# pcb_throughhole.net
KiCad netlist of a schematic drawn in EAGLE
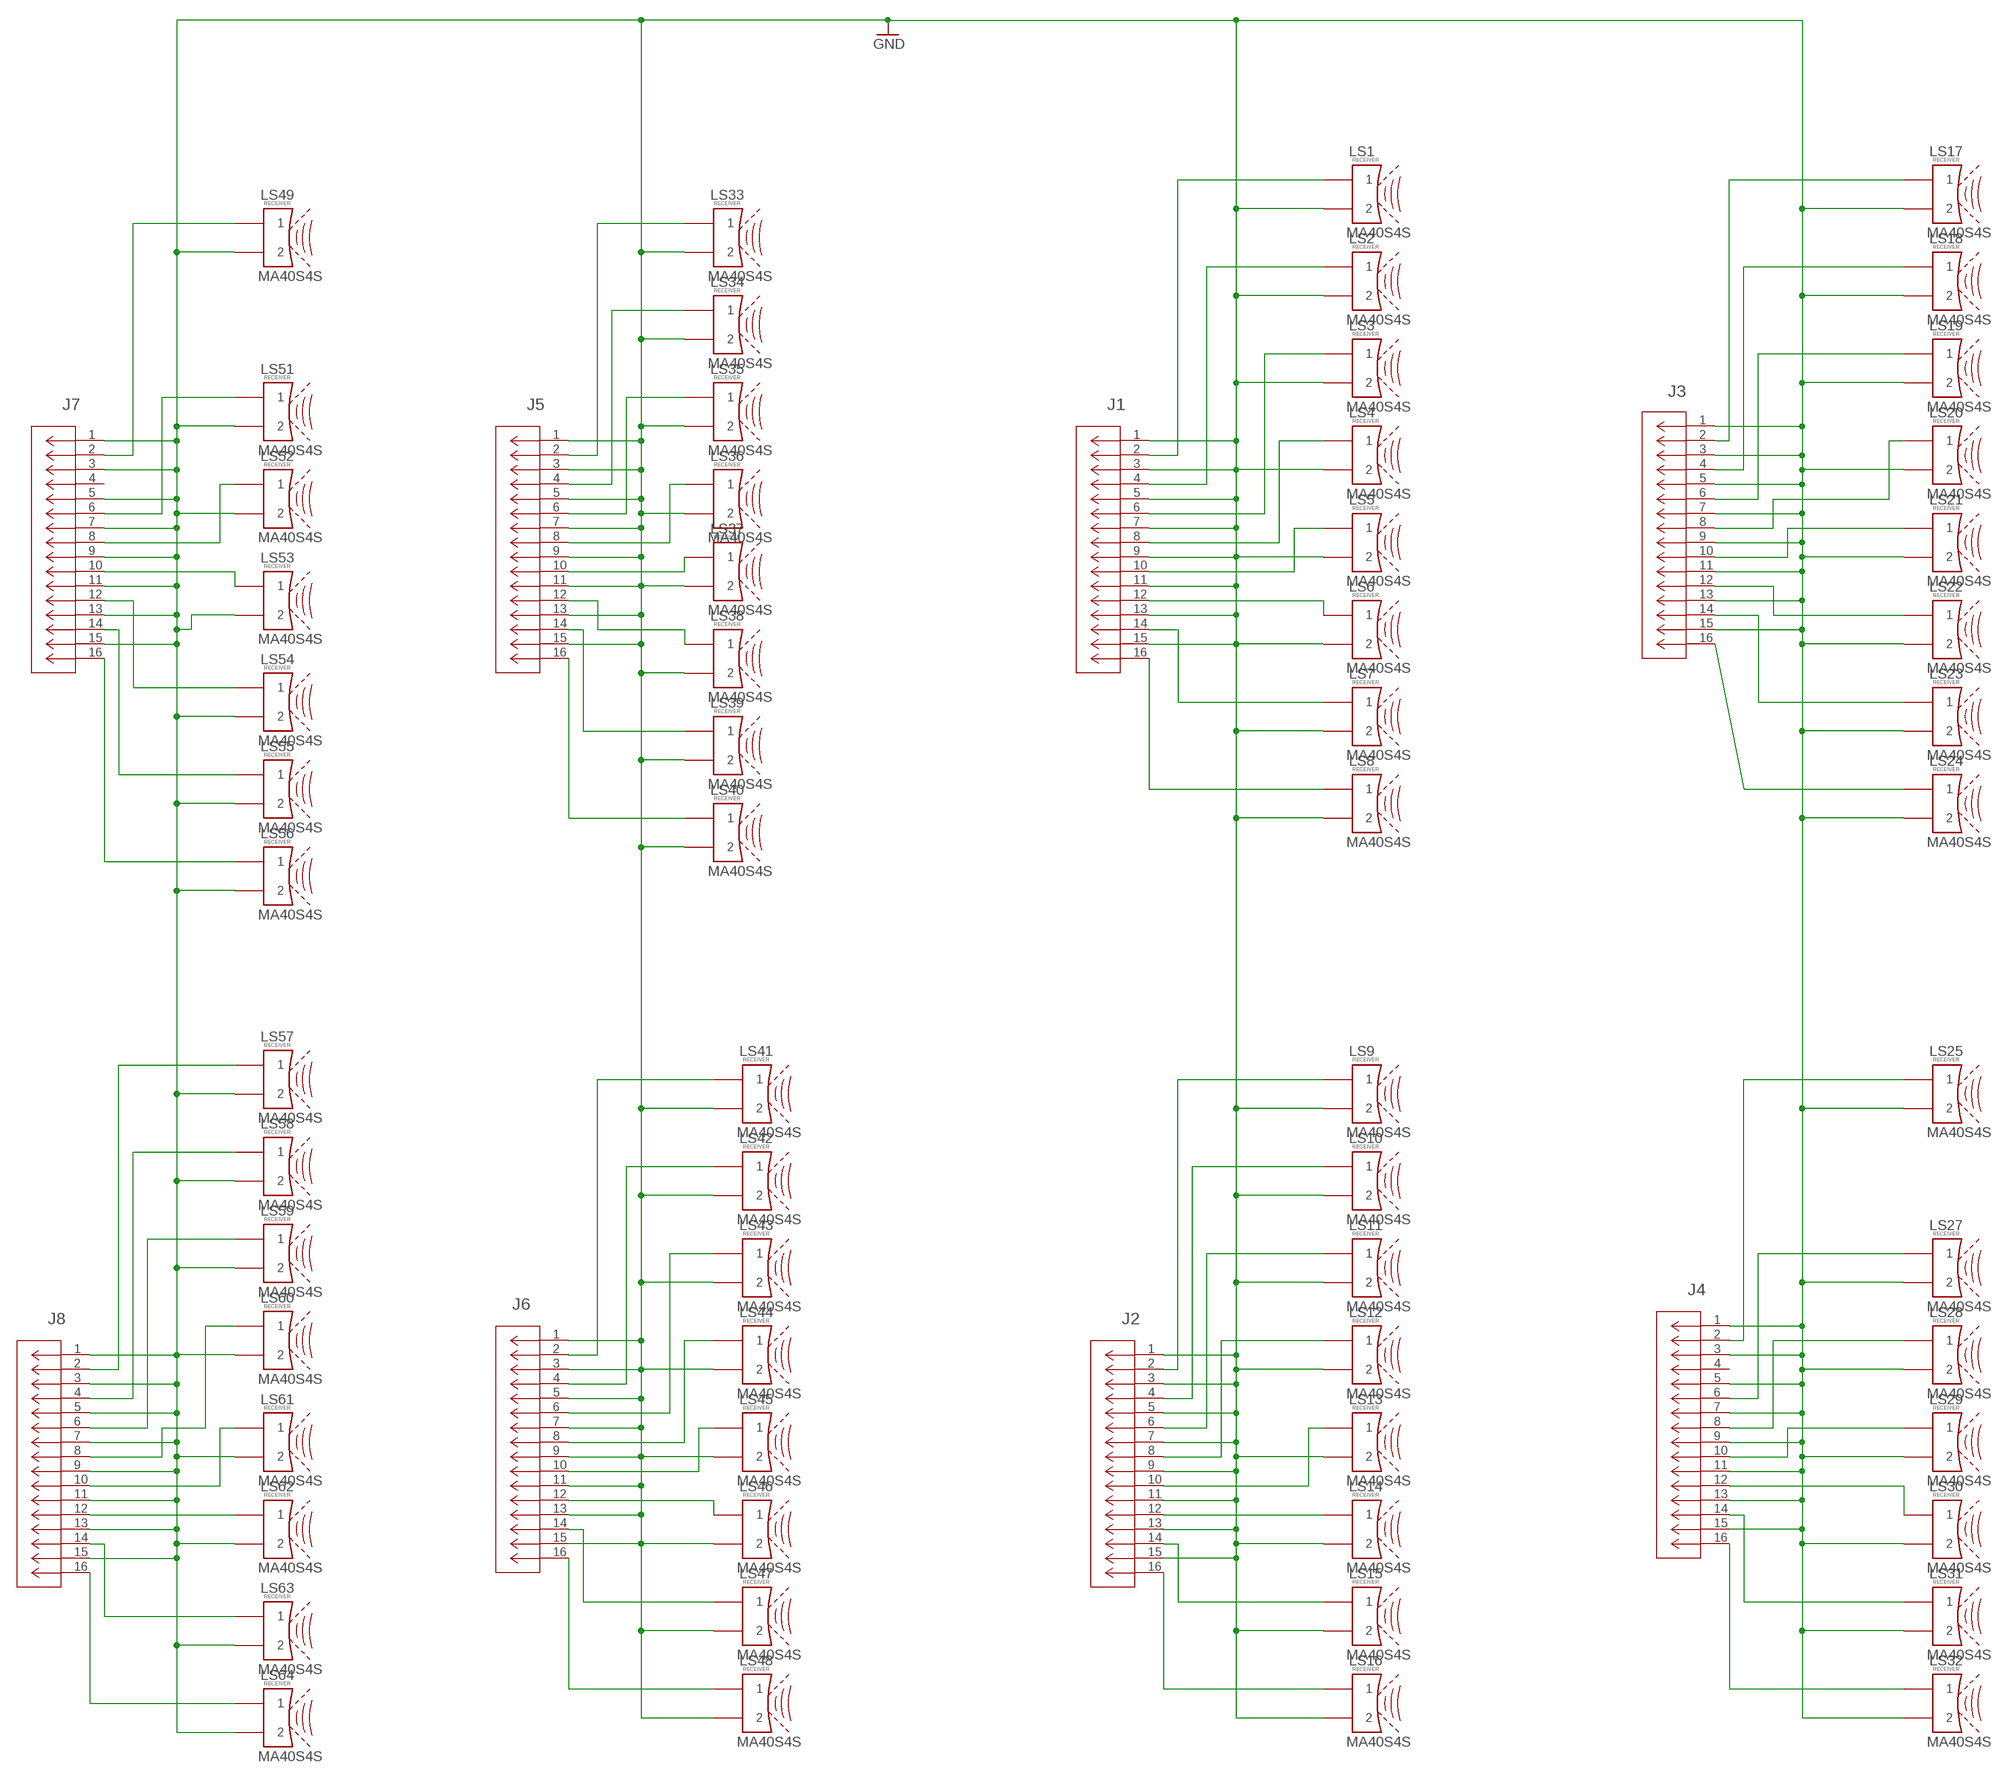
[diagram p0: schematic, sheet 1]

(export (version "E")
  (design (tool "Eeschema 10.0.6"))
  (components
    (comp (ref "J1")
      (value "70246-1201")
      (footprint "eagle-import:CONN_70246-1201_MOL")
      (fields (field (name "COPYRIGHT") "Copyright (C) 2018 Accelerated Designs. All rights reserved"))
      (libsource (lib "eagle-import") (part "70246-1201"))
    )
    (comp (ref "J2")
      (value "70246-1201")
      (footprint "eagle-import:CONN_70246-1201_MOL")
      (fields (field (name "COPYRIGHT") "Copyright (C) 2018 Accelerated Designs. All rights reserved"))
      (libsource (lib "eagle-import") (part "70246-1201"))
    )
    (comp (ref "J3")
      (value "70246-1201")
      (footprint "eagle-import:CONN_70246-1201_MOL")
      (fields (field (name "COPYRIGHT") "Copyright (C) 2018 Accelerated Designs. All rights reserved"))
      (libsource (lib "eagle-import") (part "70246-1201"))
    )
    (comp (ref "J4")
      (value "70246-1201")
      (footprint "eagle-import:CONN_70246-1201_MOL")
      (fields (field (name "COPYRIGHT") "Copyright (C) 2018 Accelerated Designs. All rights reserved"))
      (libsource (lib "eagle-import") (part "70246-1201"))
    )
    (comp (ref "J5")
      (value "70246-1201")
      (footprint "eagle-import:CONN_70246-1201_MOL")
      (fields (field (name "COPYRIGHT") "Copyright (C) 2018 Accelerated Designs. All rights reserved"))
      (libsource (lib "eagle-import") (part "70246-1201"))
    )
    (comp (ref "J6")
      (value "70246-1201")
      (footprint "eagle-import:CONN_70246-1201_MOL")
      (fields (field (name "COPYRIGHT") "Copyright (C) 2018 Accelerated Designs. All rights reserved"))
      (libsource (lib "eagle-import") (part "70246-1201"))
    )
    (comp (ref "J7")
      (value "70246-1201")
      (footprint "eagle-import:CONN_70246-1201_MOL")
      (fields (field (name "COPYRIGHT") "Copyright (C) 2018 Accelerated Designs. All rights reserved"))
      (libsource (lib "eagle-import") (part "70246-1201"))
    )
    (comp (ref "J8")
      (value "70246-1201")
      (footprint "eagle-import:CONN_70246-1201_MOL")
      (fields (field (name "COPYRIGHT") "Copyright (C) 2018 Accelerated Designs. All rights reserved"))
      (libsource (lib "eagle-import") (part "70246-1201"))
    )
    (comp (ref "LS1")
      (value "MA40S4S")
      (footprint "eagle-import:XDCR_MA40S4S")
      (fields (field (name "MF") "Murata"))
      (libsource (lib "eagle-import") (part "MA40S4S"))
    )
    (comp (ref "LS2")
      (value "MA40S4S")
      (footprint "eagle-import:XDCR_MA40S4S")
      (fields (field (name "MF") "Murata"))
      (libsource (lib "eagle-import") (part "MA40S4S"))
    )
    (comp (ref "LS3")
      (value "MA40S4S")
      (footprint "eagle-import:XDCR_MA40S4S")
      (fields (field (name "MF") "Murata"))
      (libsource (lib "eagle-import") (part "MA40S4S"))
    )
    (comp (ref "LS4")
      (value "MA40S4S")
      (footprint "eagle-import:XDCR_MA40S4S")
      (fields (field (name "MF") "Murata"))
      (libsource (lib "eagle-import") (part "MA40S4S"))
    )
    (comp (ref "LS5")
      (value "MA40S4S")
      (footprint "eagle-import:XDCR_MA40S4S")
      (fields (field (name "MF") "Murata"))
      (libsource (lib "eagle-import") (part "MA40S4S"))
    )
    (comp (ref "LS6")
      (value "MA40S4S")
      (footprint "eagle-import:XDCR_MA40S4S")
      (fields (field (name "MF") "Murata"))
      (libsource (lib "eagle-import") (part "MA40S4S"))
    )
    (comp (ref "LS7")
      (value "MA40S4S")
      (footprint "eagle-import:XDCR_MA40S4S")
      (fields (field (name "MF") "Murata"))
      (libsource (lib "eagle-import") (part "MA40S4S"))
    )
    (comp (ref "LS8")
      (value "MA40S4S")
      (footprint "eagle-import:XDCR_MA40S4S")
      (fields (field (name "MF") "Murata"))
      (libsource (lib "eagle-import") (part "MA40S4S"))
    )
    (comp (ref "LS9")
      (value "MA40S4S")
      (footprint "eagle-import:XDCR_MA40S4S")
      (fields (field (name "MF") "Murata"))
      (libsource (lib "eagle-import") (part "MA40S4S"))
    )
    (comp (ref "LS10")
      (value "MA40S4S")
      (footprint "eagle-import:XDCR_MA40S4S")
      (fields (field (name "MF") "Murata"))
      (libsource (lib "eagle-import") (part "MA40S4S"))
    )
    (comp (ref "LS11")
      (value "MA40S4S")
      (footprint "eagle-import:XDCR_MA40S4S")
      (fields (field (name "MF") "Murata"))
      (libsource (lib "eagle-import") (part "MA40S4S"))
    )
    (comp (ref "LS12")
      (value "MA40S4S")
      (footprint "eagle-import:XDCR_MA40S4S")
      (fields (field (name "MF") "Murata"))
      (libsource (lib "eagle-import") (part "MA40S4S"))
    )
    (comp (ref "LS13")
      (value "MA40S4S")
      (footprint "eagle-import:XDCR_MA40S4S")
      (fields (field (name "MF") "Murata"))
      (libsource (lib "eagle-import") (part "MA40S4S"))
    )
    (comp (ref "LS14")
      (value "MA40S4S")
      (footprint "eagle-import:XDCR_MA40S4S")
      (fields (field (name "MF") "Murata"))
      (libsource (lib "eagle-import") (part "MA40S4S"))
    )
    (comp (ref "LS15")
      (value "MA40S4S")
      (footprint "eagle-import:XDCR_MA40S4S")
      (fields (field (name "MF") "Murata"))
      (libsource (lib "eagle-import") (part "MA40S4S"))
    )
    (comp (ref "LS16")
      (value "MA40S4S")
      (footprint "eagle-import:XDCR_MA40S4S")
      (fields (field (name "MF") "Murata"))
      (libsource (lib "eagle-import") (part "MA40S4S"))
    )
    (comp (ref "LS17")
      (value "MA40S4S")
      (footprint "eagle-import:XDCR_MA40S4S")
      (fields (field (name "MF") "Murata"))
      (libsource (lib "eagle-import") (part "MA40S4S"))
    )
    (comp (ref "LS18")
      (value "MA40S4S")
      (footprint "eagle-import:XDCR_MA40S4S")
      (fields (field (name "MF") "Murata"))
      (libsource (lib "eagle-import") (part "MA40S4S"))
    )
    (comp (ref "LS19")
      (value "MA40S4S")
      (footprint "eagle-import:XDCR_MA40S4S")
      (fields (field (name "MF") "Murata"))
      (libsource (lib "eagle-import") (part "MA40S4S"))
    )
    (comp (ref "LS20")
      (value "MA40S4S")
      (footprint "eagle-import:XDCR_MA40S4S")
      (fields (field (name "MF") "Murata"))
      (libsource (lib "eagle-import") (part "MA40S4S"))
    )
    (comp (ref "LS21")
      (value "MA40S4S")
      (footprint "eagle-import:XDCR_MA40S4S")
      (fields (field (name "MF") "Murata"))
      (libsource (lib "eagle-import") (part "MA40S4S"))
    )
    (comp (ref "LS22")
      (value "MA40S4S")
      (footprint "eagle-import:XDCR_MA40S4S")
      (fields (field (name "MF") "Murata"))
      (libsource (lib "eagle-import") (part "MA40S4S"))
    )
    (comp (ref "LS23")
      (value "MA40S4S")
      (footprint "eagle-import:XDCR_MA40S4S")
      (fields (field (name "MF") "Murata"))
      (libsource (lib "eagle-import") (part "MA40S4S"))
    )
    (comp (ref "LS24")
      (value "MA40S4S")
      (footprint "eagle-import:XDCR_MA40S4S")
      (fields (field (name "MF") "Murata"))
      (libsource (lib "eagle-import") (part "MA40S4S"))
    )
    (comp (ref "LS25")
      (value "MA40S4S")
      (footprint "eagle-import:XDCR_MA40S4S")
      (fields (field (name "MF") "Murata"))
      (libsource (lib "eagle-import") (part "MA40S4S"))
    )
    (comp (ref "LS27")
      (value "MA40S4S")
      (footprint "eagle-import:XDCR_MA40S4S")
      (fields (field (name "MF") "Murata"))
      (libsource (lib "eagle-import") (part "MA40S4S"))
    )
    (comp (ref "LS28")
      (value "MA40S4S")
      (footprint "eagle-import:XDCR_MA40S4S")
      (fields (field (name "MF") "Murata"))
      (libsource (lib "eagle-import") (part "MA40S4S"))
    )
    (comp (ref "LS29")
      (value "MA40S4S")
      (footprint "eagle-import:XDCR_MA40S4S")
      (fields (field (name "MF") "Murata"))
      (libsource (lib "eagle-import") (part "MA40S4S"))
    )
    (comp (ref "LS30")
      (value "MA40S4S")
      (footprint "eagle-import:XDCR_MA40S4S")
      (fields (field (name "MF") "Murata"))
      (libsource (lib "eagle-import") (part "MA40S4S"))
    )
    (comp (ref "LS31")
      (value "MA40S4S")
      (footprint "eagle-import:XDCR_MA40S4S")
      (fields (field (name "MF") "Murata"))
      (libsource (lib "eagle-import") (part "MA40S4S"))
    )
    (comp (ref "LS32")
      (value "MA40S4S")
      (footprint "eagle-import:XDCR_MA40S4S")
      (fields (field (name "MF") "Murata"))
      (libsource (lib "eagle-import") (part "MA40S4S"))
    )
    (comp (ref "LS33")
      (value "MA40S4S")
      (footprint "eagle-import:XDCR_MA40S4S")
      (fields (field (name "MF") "Murata"))
      (libsource (lib "eagle-import") (part "MA40S4S"))
    )
    (comp (ref "LS34")
      (value "MA40S4S")
      (footprint "eagle-import:XDCR_MA40S4S")
      (fields (field (name "MF") "Murata"))
      (libsource (lib "eagle-import") (part "MA40S4S"))
    )
    (comp (ref "LS35")
      (value "MA40S4S")
      (footprint "eagle-import:XDCR_MA40S4S")
      (fields (field (name "MF") "Murata"))
      (libsource (lib "eagle-import") (part "MA40S4S"))
    )
    (comp (ref "LS36")
      (value "MA40S4S")
      (footprint "eagle-import:XDCR_MA40S4S")
      (fields (field (name "MF") "Murata"))
      (libsource (lib "eagle-import") (part "MA40S4S"))
    )
    (comp (ref "LS37")
      (value "MA40S4S")
      (footprint "eagle-import:XDCR_MA40S4S")
      (fields (field (name "MF") "Murata"))
      (libsource (lib "eagle-import") (part "MA40S4S"))
    )
    (comp (ref "LS38")
      (value "MA40S4S")
      (footprint "eagle-import:XDCR_MA40S4S")
      (fields (field (name "MF") "Murata"))
      (libsource (lib "eagle-import") (part "MA40S4S"))
    )
    (comp (ref "LS39")
      (value "MA40S4S")
      (footprint "eagle-import:XDCR_MA40S4S")
      (fields (field (name "MF") "Murata"))
      (libsource (lib "eagle-import") (part "MA40S4S"))
    )
    (comp (ref "LS40")
      (value "MA40S4S")
      (footprint "eagle-import:XDCR_MA40S4S")
      (fields (field (name "MF") "Murata"))
      (libsource (lib "eagle-import") (part "MA40S4S"))
    )
    (comp (ref "LS41")
      (value "MA40S4S")
      (footprint "eagle-import:XDCR_MA40S4S")
      (fields (field (name "MF") "Murata"))
      (libsource (lib "eagle-import") (part "MA40S4S"))
    )
    (comp (ref "LS42")
      (value "MA40S4S")
      (footprint "eagle-import:XDCR_MA40S4S")
      (fields (field (name "MF") "Murata"))
      (libsource (lib "eagle-import") (part "MA40S4S"))
    )
    (comp (ref "LS43")
      (value "MA40S4S")
      (footprint "eagle-import:XDCR_MA40S4S")
      (fields (field (name "MF") "Murata"))
      (libsource (lib "eagle-import") (part "MA40S4S"))
    )
    (comp (ref "LS44")
      (value "MA40S4S")
      (footprint "eagle-import:XDCR_MA40S4S")
      (fields (field (name "MF") "Murata"))
      (libsource (lib "eagle-import") (part "MA40S4S"))
    )
    (comp (ref "LS45")
      (value "MA40S4S")
      (footprint "eagle-import:XDCR_MA40S4S")
      (fields (field (name "MF") "Murata"))
      (libsource (lib "eagle-import") (part "MA40S4S"))
    )
    (comp (ref "LS46")
      (value "MA40S4S")
      (footprint "eagle-import:XDCR_MA40S4S")
      (fields (field (name "MF") "Murata"))
      (libsource (lib "eagle-import") (part "MA40S4S"))
    )
    (comp (ref "LS47")
      (value "MA40S4S")
      (footprint "eagle-import:XDCR_MA40S4S")
      (fields (field (name "MF") "Murata"))
      (libsource (lib "eagle-import") (part "MA40S4S"))
    )
    (comp (ref "LS48")
      (value "MA40S4S")
      (footprint "eagle-import:XDCR_MA40S4S")
      (fields (field (name "MF") "Murata"))
      (libsource (lib "eagle-import") (part "MA40S4S"))
    )
    (comp (ref "LS49")
      (value "MA40S4S")
      (footprint "eagle-import:XDCR_MA40S4S")
      (fields (field (name "MF") "Murata"))
      (libsource (lib "eagle-import") (part "MA40S4S"))
    )
    (comp (ref "LS51")
      (value "MA40S4S")
      (footprint "eagle-import:XDCR_MA40S4S")
      (fields (field (name "MF") "Murata"))
      (libsource (lib "eagle-import") (part "MA40S4S"))
    )
    (comp (ref "LS52")
      (value "MA40S4S")
      (footprint "eagle-import:XDCR_MA40S4S")
      (fields (field (name "MF") "Murata"))
      (libsource (lib "eagle-import") (part "MA40S4S"))
    )
    (comp (ref "LS53")
      (value "MA40S4S")
      (footprint "eagle-import:XDCR_MA40S4S")
      (fields (field (name "MF") "Murata"))
      (libsource (lib "eagle-import") (part "MA40S4S"))
    )
    (comp (ref "LS54")
      (value "MA40S4S")
      (footprint "eagle-import:XDCR_MA40S4S")
      (fields (field (name "MF") "Murata"))
      (libsource (lib "eagle-import") (part "MA40S4S"))
    )
    (comp (ref "LS55")
      (value "MA40S4S")
      (footprint "eagle-import:XDCR_MA40S4S")
      (fields (field (name "MF") "Murata"))
      (libsource (lib "eagle-import") (part "MA40S4S"))
    )
    (comp (ref "LS56")
      (value "MA40S4S")
      (footprint "eagle-import:XDCR_MA40S4S")
      (fields (field (name "MF") "Murata"))
      (libsource (lib "eagle-import") (part "MA40S4S"))
    )
    (comp (ref "LS57")
      (value "MA40S4S")
      (footprint "eagle-import:XDCR_MA40S4S")
      (fields (field (name "MF") "Murata"))
      (libsource (lib "eagle-import") (part "MA40S4S"))
    )
    (comp (ref "LS58")
      (value "MA40S4S")
      (footprint "eagle-import:XDCR_MA40S4S")
      (fields (field (name "MF") "Murata"))
      (libsource (lib "eagle-import") (part "MA40S4S"))
    )
    (comp (ref "LS59")
      (value "MA40S4S")
      (footprint "eagle-import:XDCR_MA40S4S")
      (fields (field (name "MF") "Murata"))
      (libsource (lib "eagle-import") (part "MA40S4S"))
    )
    (comp (ref "LS60")
      (value "MA40S4S")
      (footprint "eagle-import:XDCR_MA40S4S")
      (fields (field (name "MF") "Murata"))
      (libsource (lib "eagle-import") (part "MA40S4S"))
    )
    (comp (ref "LS61")
      (value "MA40S4S")
      (footprint "eagle-import:XDCR_MA40S4S")
      (fields (field (name "MF") "Murata"))
      (libsource (lib "eagle-import") (part "MA40S4S"))
    )
    (comp (ref "LS62")
      (value "MA40S4S")
      (footprint "eagle-import:XDCR_MA40S4S")
      (fields (field (name "MF") "Murata"))
      (libsource (lib "eagle-import") (part "MA40S4S"))
    )
    (comp (ref "LS63")
      (value "MA40S4S")
      (footprint "eagle-import:XDCR_MA40S4S")
      (fields (field (name "MF") "Murata"))
      (libsource (lib "eagle-import") (part "MA40S4S"))
    )
    (comp (ref "LS64")
      (value "MA40S4S")
      (footprint "eagle-import:XDCR_MA40S4S")
      (fields (field (name "MF") "Murata"))
      (libsource (lib "eagle-import") (part "MA40S4S"))
    )
  )
  (nets
    (net (code "1") (name "GND") (class "Default")
      (node (ref "J1") (pin "1") (pinfunction "1_1") (pintype "passive"))
      (node (ref "J1") (pin "11") (pinfunction "11_11") (pintype "passive"))
      (node (ref "J1") (pin "13") (pinfunction "13_13") (pintype "passive"))
      (node (ref "J1") (pin "15") (pinfunction "15_15") (pintype "passive"))
      (node (ref "J1") (pin "3") (pinfunction "3_3") (pintype "passive"))
      (node (ref "J1") (pin "5") (pinfunction "5_5") (pintype "passive"))
      (node (ref "J1") (pin "7") (pinfunction "7_7") (pintype "passive"))
      (node (ref "J1") (pin "9") (pinfunction "9_9") (pintype "passive"))
      (node (ref "J2") (pin "1") (pinfunction "1_1") (pintype "passive"))
      (node (ref "J2") (pin "11") (pinfunction "11_11") (pintype "passive"))
      (node (ref "J2") (pin "13") (pinfunction "13_13") (pintype "passive"))
      (node (ref "J2") (pin "15") (pinfunction "15_15") (pintype "passive"))
      (node (ref "J2") (pin "3") (pinfunction "3_3") (pintype "passive"))
      (node (ref "J2") (pin "5") (pinfunction "5_5") (pintype "passive"))
      (node (ref "J2") (pin "7") (pinfunction "7_7") (pintype "passive"))
      (node (ref "J2") (pin "9") (pinfunction "9_9") (pintype "passive"))
      (node (ref "J3") (pin "1") (pinfunction "1_1") (pintype "passive"))
      (node (ref "J3") (pin "11") (pinfunction "11_11") (pintype "passive"))
      (node (ref "J3") (pin "13") (pinfunction "13_13") (pintype "passive"))
      (node (ref "J3") (pin "15") (pinfunction "15_15") (pintype "passive"))
      (node (ref "J3") (pin "3") (pinfunction "3_3") (pintype "passive"))
      (node (ref "J3") (pin "5") (pinfunction "5_5") (pintype "passive"))
      (node (ref "J3") (pin "7") (pinfunction "7_7") (pintype "passive"))
      (node (ref "J3") (pin "9") (pinfunction "9_9") (pintype "passive"))
      (node (ref "J4") (pin "1") (pinfunction "1_1") (pintype "passive"))
      (node (ref "J4") (pin "11") (pinfunction "11_11") (pintype "passive"))
      (node (ref "J4") (pin "13") (pinfunction "13_13") (pintype "passive"))
      (node (ref "J4") (pin "15") (pinfunction "15_15") (pintype "passive"))
      (node (ref "J4") (pin "3") (pinfunction "3_3") (pintype "passive"))
      (node (ref "J4") (pin "5") (pinfunction "5_5") (pintype "passive"))
      (node (ref "J4") (pin "7") (pinfunction "7_7") (pintype "passive"))
      (node (ref "J4") (pin "9") (pinfunction "9_9") (pintype "passive"))
      (node (ref "J5") (pin "1") (pinfunction "1_1") (pintype "passive"))
      (node (ref "J5") (pin "11") (pinfunction "11_11") (pintype "passive"))
      (node (ref "J5") (pin "13") (pinfunction "13_13") (pintype "passive"))
      (node (ref "J5") (pin "15") (pinfunction "15_15") (pintype "passive"))
      (node (ref "J5") (pin "3") (pinfunction "3_3") (pintype "passive"))
      (node (ref "J5") (pin "5") (pinfunction "5_5") (pintype "passive"))
      (node (ref "J5") (pin "7") (pinfunction "7_7") (pintype "passive"))
      (node (ref "J5") (pin "9") (pinfunction "9_9") (pintype "passive"))
      (node (ref "J6") (pin "1") (pinfunction "1_1") (pintype "passive"))
      (node (ref "J6") (pin "11") (pinfunction "11_11") (pintype "passive"))
      (node (ref "J6") (pin "13") (pinfunction "13_13") (pintype "passive"))
      (node (ref "J6") (pin "15") (pinfunction "15_15") (pintype "passive"))
      (node (ref "J6") (pin "3") (pinfunction "3_3") (pintype "passive"))
      (node (ref "J6") (pin "5") (pinfunction "5_5") (pintype "passive"))
      (node (ref "J6") (pin "7") (pinfunction "7_7") (pintype "passive"))
      (node (ref "J6") (pin "9") (pinfunction "9_9") (pintype "passive"))
      (node (ref "J7") (pin "1") (pinfunction "1_1") (pintype "passive"))
      (node (ref "J7") (pin "11") (pinfunction "11_11") (pintype "passive"))
      (node (ref "J7") (pin "13") (pinfunction "13_13") (pintype "passive"))
      (node (ref "J7") (pin "15") (pinfunction "15_15") (pintype "passive"))
      (node (ref "J7") (pin "3") (pinfunction "3_3") (pintype "passive"))
      (node (ref "J7") (pin "5") (pinfunction "5_5") (pintype "passive"))
      (node (ref "J7") (pin "7") (pinfunction "7_7") (pintype "passive"))
      (node (ref "J7") (pin "9") (pinfunction "9_9") (pintype "passive"))
      (node (ref "J8") (pin "1") (pinfunction "1_1") (pintype "passive"))
      (node (ref "J8") (pin "11") (pinfunction "11_11") (pintype "passive"))
      (node (ref "J8") (pin "13") (pinfunction "13_13") (pintype "passive"))
      (node (ref "J8") (pin "15") (pinfunction "15_15") (pintype "passive"))
      (node (ref "J8") (pin "3") (pinfunction "3_3") (pintype "passive"))
      (node (ref "J8") (pin "5") (pinfunction "5_5") (pintype "passive"))
      (node (ref "J8") (pin "7") (pinfunction "7_7") (pintype "passive"))
      (node (ref "J8") (pin "9") (pinfunction "9_9") (pintype "passive"))
      (node (ref "LS1") (pin "2") (pinfunction "2_2") (pintype "passive"))
      (node (ref "LS10") (pin "2") (pinfunction "2_2") (pintype "passive"))
      (node (ref "LS11") (pin "2") (pinfunction "2_2") (pintype "passive"))
      (node (ref "LS12") (pin "2") (pinfunction "2_2") (pintype "passive"))
      (node (ref "LS13") (pin "2") (pinfunction "2_2") (pintype "passive"))
      (node (ref "LS14") (pin "2") (pinfunction "2_2") (pintype "passive"))
      (node (ref "LS15") (pin "2") (pinfunction "2_2") (pintype "passive"))
      (node (ref "LS16") (pin "2") (pinfunction "2_2") (pintype "passive"))
      (node (ref "LS17") (pin "2") (pinfunction "2_2") (pintype "passive"))
      (node (ref "LS18") (pin "2") (pinfunction "2_2") (pintype "passive"))
      (node (ref "LS19") (pin "2") (pinfunction "2_2") (pintype "passive"))
      (node (ref "LS2") (pin "2") (pinfunction "2_2") (pintype "passive"))
      (node (ref "LS20") (pin "2") (pinfunction "2_2") (pintype "passive"))
      (node (ref "LS21") (pin "2") (pinfunction "2_2") (pintype "passive"))
      (node (ref "LS22") (pin "2") (pinfunction "2_2") (pintype "passive"))
      (node (ref "LS23") (pin "2") (pinfunction "2_2") (pintype "passive"))
      (node (ref "LS24") (pin "2") (pinfunction "2_2") (pintype "passive"))
      (node (ref "LS25") (pin "2") (pinfunction "2_2") (pintype "passive"))
      (node (ref "LS27") (pin "2") (pinfunction "2_2") (pintype "passive"))
      (node (ref "LS28") (pin "2") (pinfunction "2_2") (pintype "passive"))
      (node (ref "LS29") (pin "2") (pinfunction "2_2") (pintype "passive"))
      (node (ref "LS3") (pin "2") (pinfunction "2_2") (pintype "passive"))
      (node (ref "LS30") (pin "2") (pinfunction "2_2") (pintype "passive"))
      (node (ref "LS31") (pin "2") (pinfunction "2_2") (pintype "passive"))
      (node (ref "LS32") (pin "2") (pinfunction "2_2") (pintype "passive"))
      (node (ref "LS33") (pin "2") (pinfunction "2_2") (pintype "passive"))
      (node (ref "LS34") (pin "2") (pinfunction "2_2") (pintype "passive"))
      (node (ref "LS35") (pin "2") (pinfunction "2_2") (pintype "passive"))
      (node (ref "LS36") (pin "2") (pinfunction "2_2") (pintype "passive"))
      (node (ref "LS37") (pin "2") (pinfunction "2_2") (pintype "passive"))
      (node (ref "LS38") (pin "2") (pinfunction "2_2") (pintype "passive"))
      (node (ref "LS39") (pin "2") (pinfunction "2_2") (pintype "passive"))
      (node (ref "LS4") (pin "2") (pinfunction "2_2") (pintype "passive"))
      (node (ref "LS40") (pin "2") (pinfunction "2_2") (pintype "passive"))
      (node (ref "LS41") (pin "2") (pinfunction "2_2") (pintype "passive"))
      (node (ref "LS42") (pin "2") (pinfunction "2_2") (pintype "passive"))
      (node (ref "LS43") (pin "2") (pinfunction "2_2") (pintype "passive"))
      (node (ref "LS44") (pin "2") (pinfunction "2_2") (pintype "passive"))
      (node (ref "LS45") (pin "2") (pinfunction "2_2") (pintype "passive"))
      (node (ref "LS46") (pin "2") (pinfunction "2_2") (pintype "passive"))
      (node (ref "LS47") (pin "2") (pinfunction "2_2") (pintype "passive"))
      (node (ref "LS48") (pin "2") (pinfunction "2_2") (pintype "passive"))
      (node (ref "LS49") (pin "2") (pinfunction "2_2") (pintype "passive"))
      (node (ref "LS5") (pin "2") (pinfunction "2_2") (pintype "passive"))
      (node (ref "LS51") (pin "2") (pinfunction "2_2") (pintype "passive"))
      (node (ref "LS52") (pin "2") (pinfunction "2_2") (pintype "passive"))
      (node (ref "LS53") (pin "2") (pinfunction "2_2") (pintype "passive"))
      (node (ref "LS54") (pin "2") (pinfunction "2_2") (pintype "passive"))
      (node (ref "LS55") (pin "2") (pinfunction "2_2") (pintype "passive"))
      (node (ref "LS56") (pin "2") (pinfunction "2_2") (pintype "passive"))
      (node (ref "LS57") (pin "2") (pinfunction "2_2") (pintype "passive"))
      (node (ref "LS58") (pin "2") (pinfunction "2_2") (pintype "passive"))
      (node (ref "LS59") (pin "2") (pinfunction "2_2") (pintype "passive"))
      (node (ref "LS6") (pin "2") (pinfunction "2_2") (pintype "passive"))
      (node (ref "LS60") (pin "2") (pinfunction "2_2") (pintype "passive"))
      (node (ref "LS61") (pin "2") (pinfunction "2_2") (pintype "passive"))
      (node (ref "LS62") (pin "2") (pinfunction "2_2") (pintype "passive"))
      (node (ref "LS63") (pin "2") (pinfunction "2_2") (pintype "passive"))
      (node (ref "LS64") (pin "2") (pinfunction "2_2") (pintype "passive"))
      (node (ref "LS7") (pin "2") (pinfunction "2_2") (pintype "passive"))
      (node (ref "LS8") (pin "2") (pinfunction "2_2") (pintype "passive"))
      (node (ref "LS9") (pin "2") (pinfunction "2_2") (pintype "passive"))
    )
    (net (code "2") (name "Net-(J1-Pad2)") (class "Default")
      (node (ref "J1") (pin "2") (pinfunction "2_2") (pintype "passive"))
      (node (ref "LS1") (pin "1") (pinfunction "1_1") (pintype "passive"))
    )
    (net (code "3") (name "Net-(J1-Pad4)") (class "Default")
      (node (ref "J1") (pin "4") (pinfunction "4_4") (pintype "passive"))
      (node (ref "LS2") (pin "1") (pinfunction "1_1") (pintype "passive"))
    )
    (net (code "4") (name "Net-(J1-Pad6)") (class "Default")
      (node (ref "J1") (pin "6") (pinfunction "6_6") (pintype "passive"))
      (node (ref "LS3") (pin "1") (pinfunction "1_1") (pintype "passive"))
    )
    (net (code "5") (name "Net-(J1-Pad8)") (class "Default")
      (node (ref "J1") (pin "8") (pinfunction "8_8") (pintype "passive"))
      (node (ref "LS4") (pin "1") (pinfunction "1_1") (pintype "passive"))
    )
    (net (code "6") (name "Net-(J1-Pad10)") (class "Default")
      (node (ref "J1") (pin "10") (pinfunction "10_10") (pintype "passive"))
      (node (ref "LS5") (pin "1") (pinfunction "1_1") (pintype "passive"))
    )
    (net (code "7") (name "Net-(J1-Pad12)") (class "Default")
      (node (ref "J1") (pin "12") (pinfunction "12_12") (pintype "passive"))
      (node (ref "LS6") (pin "1") (pinfunction "1_1") (pintype "passive"))
    )
    (net (code "8") (name "Net-(J1-Pad14)") (class "Default")
      (node (ref "J1") (pin "14") (pinfunction "14_14") (pintype "passive"))
      (node (ref "LS7") (pin "1") (pinfunction "1_1") (pintype "passive"))
    )
    (net (code "9") (name "Net-(J1-Pad16)") (class "Default")
      (node (ref "J1") (pin "16") (pinfunction "16_16") (pintype "passive"))
      (node (ref "LS8") (pin "1") (pinfunction "1_1") (pintype "passive"))
    )
    (net (code "10") (name "Net-(J2-Pad2)") (class "Default")
      (node (ref "J2") (pin "2") (pinfunction "2_2") (pintype "passive"))
      (node (ref "LS9") (pin "1") (pinfunction "1_1") (pintype "passive"))
    )
    (net (code "11") (name "Net-(J2-Pad4)") (class "Default")
      (node (ref "J2") (pin "4") (pinfunction "4_4") (pintype "passive"))
      (node (ref "LS10") (pin "1") (pinfunction "1_1") (pintype "passive"))
    )
    (net (code "12") (name "Net-(J2-Pad6)") (class "Default")
      (node (ref "J2") (pin "6") (pinfunction "6_6") (pintype "passive"))
      (node (ref "LS11") (pin "1") (pinfunction "1_1") (pintype "passive"))
    )
    (net (code "13") (name "Net-(J2-Pad8)") (class "Default")
      (node (ref "J2") (pin "8") (pinfunction "8_8") (pintype "passive"))
      (node (ref "LS12") (pin "1") (pinfunction "1_1") (pintype "passive"))
    )
    (net (code "14") (name "Net-(J2-Pad10)") (class "Default")
      (node (ref "J2") (pin "10") (pinfunction "10_10") (pintype "passive"))
      (node (ref "LS13") (pin "1") (pinfunction "1_1") (pintype "passive"))
    )
    (net (code "15") (name "Net-(J2-Pad12)") (class "Default")
      (node (ref "J2") (pin "12") (pinfunction "12_12") (pintype "passive"))
      (node (ref "LS14") (pin "1") (pinfunction "1_1") (pintype "passive"))
    )
    (net (code "16") (name "Net-(J2-Pad14)") (class "Default")
      (node (ref "J2") (pin "14") (pinfunction "14_14") (pintype "passive"))
      (node (ref "LS15") (pin "1") (pinfunction "1_1") (pintype "passive"))
    )
    (net (code "17") (name "Net-(J2-Pad16)") (class "Default")
      (node (ref "J2") (pin "16") (pinfunction "16_16") (pintype "passive"))
      (node (ref "LS16") (pin "1") (pinfunction "1_1") (pintype "passive"))
    )
    (net (code "18") (name "Net-(J3-Pad2)") (class "Default")
      (node (ref "J3") (pin "2") (pinfunction "2_2") (pintype "passive"))
      (node (ref "LS17") (pin "1") (pinfunction "1_1") (pintype "passive"))
    )
    (net (code "19") (name "Net-(J3-Pad4)") (class "Default")
      (node (ref "J3") (pin "4") (pinfunction "4_4") (pintype "passive"))
      (node (ref "LS18") (pin "1") (pinfunction "1_1") (pintype "passive"))
    )
    (net (code "20") (name "Net-(J3-Pad6)") (class "Default")
      (node (ref "J3") (pin "6") (pinfunction "6_6") (pintype "passive"))
      (node (ref "LS19") (pin "1") (pinfunction "1_1") (pintype "passive"))
    )
    (net (code "21") (name "Net-(J3-Pad8)") (class "Default")
      (node (ref "J3") (pin "8") (pinfunction "8_8") (pintype "passive"))
      (node (ref "LS20") (pin "1") (pinfunction "1_1") (pintype "passive"))
    )
    (net (code "22") (name "Net-(J3-Pad10)") (class "Default")
      (node (ref "J3") (pin "10") (pinfunction "10_10") (pintype "passive"))
      (node (ref "LS21") (pin "1") (pinfunction "1_1") (pintype "passive"))
    )
    (net (code "23") (name "Net-(J3-Pad12)") (class "Default")
      (node (ref "J3") (pin "12") (pinfunction "12_12") (pintype "passive"))
      (node (ref "LS22") (pin "1") (pinfunction "1_1") (pintype "passive"))
    )
    (net (code "24") (name "Net-(J3-Pad14)") (class "Default")
      (node (ref "J3") (pin "14") (pinfunction "14_14") (pintype "passive"))
      (node (ref "LS23") (pin "1") (pinfunction "1_1") (pintype "passive"))
    )
    (net (code "25") (name "Net-(J3-Pad16)") (class "Default")
      (node (ref "J3") (pin "16") (pinfunction "16_16") (pintype "passive"))
      (node (ref "LS24") (pin "1") (pinfunction "1_1") (pintype "passive"))
    )
    (net (code "26") (name "Net-(J4-Pad2)") (class "Default")
      (node (ref "J4") (pin "2") (pinfunction "2_2") (pintype "passive"))
      (node (ref "LS25") (pin "1") (pinfunction "1_1") (pintype "passive"))
    )
    (net (code "27") (name "Net-(J4-Pad6)") (class "Default")
      (node (ref "J4") (pin "6") (pinfunction "6_6") (pintype "passive"))
      (node (ref "LS27") (pin "1") (pinfunction "1_1") (pintype "passive"))
    )
    (net (code "28") (name "Net-(J4-Pad8)") (class "Default")
      (node (ref "J4") (pin "8") (pinfunction "8_8") (pintype "passive"))
      (node (ref "LS28") (pin "1") (pinfunction "1_1") (pintype "passive"))
    )
    (net (code "29") (name "Net-(J4-Pad10)") (class "Default")
      (node (ref "J4") (pin "10") (pinfunction "10_10") (pintype "passive"))
      (node (ref "LS29") (pin "1") (pinfunction "1_1") (pintype "passive"))
    )
    (net (code "30") (name "Net-(J4-Pad12)") (class "Default")
      (node (ref "J4") (pin "12") (pinfunction "12_12") (pintype "passive"))
      (node (ref "LS30") (pin "1") (pinfunction "1_1") (pintype "passive"))
    )
    (net (code "31") (name "Net-(J4-Pad14)") (class "Default")
      (node (ref "J4") (pin "14") (pinfunction "14_14") (pintype "passive"))
      (node (ref "LS31") (pin "1") (pinfunction "1_1") (pintype "passive"))
    )
    (net (code "32") (name "Net-(J4-Pad16)") (class "Default")
      (node (ref "J4") (pin "16") (pinfunction "16_16") (pintype "passive"))
      (node (ref "LS32") (pin "1") (pinfunction "1_1") (pintype "passive"))
    )
    (net (code "33") (name "Net-(J5-Pad2)") (class "Default")
      (node (ref "J5") (pin "2") (pinfunction "2_2") (pintype "passive"))
      (node (ref "LS33") (pin "1") (pinfunction "1_1") (pintype "passive"))
    )
    (net (code "34") (name "Net-(J5-Pad4)") (class "Default")
      (node (ref "J5") (pin "4") (pinfunction "4_4") (pintype "passive"))
      (node (ref "LS34") (pin "1") (pinfunction "1_1") (pintype "passive"))
    )
    (net (code "35") (name "Net-(J5-Pad6)") (class "Default")
      (node (ref "J5") (pin "6") (pinfunction "6_6") (pintype "passive"))
      (node (ref "LS35") (pin "1") (pinfunction "1_1") (pintype "passive"))
    )
    (net (code "36") (name "Net-(J5-Pad8)") (class "Default")
      (node (ref "J5") (pin "8") (pinfunction "8_8") (pintype "passive"))
      (node (ref "LS36") (pin "1") (pinfunction "1_1") (pintype "passive"))
    )
    (net (code "37") (name "Net-(J5-Pad10)") (class "Default")
      (node (ref "J5") (pin "10") (pinfunction "10_10") (pintype "passive"))
      (node (ref "LS37") (pin "1") (pinfunction "1_1") (pintype "passive"))
    )
    (net (code "38") (name "Net-(J5-Pad12)") (class "Default")
      (node (ref "J5") (pin "12") (pinfunction "12_12") (pintype "passive"))
      (node (ref "LS38") (pin "1") (pinfunction "1_1") (pintype "passive"))
    )
    (net (code "39") (name "Net-(J5-Pad14)") (class "Default")
      (node (ref "J5") (pin "14") (pinfunction "14_14") (pintype "passive"))
      (node (ref "LS39") (pin "1") (pinfunction "1_1") (pintype "passive"))
    )
    (net (code "40") (name "Net-(J5-Pad16)") (class "Default")
      (node (ref "J5") (pin "16") (pinfunction "16_16") (pintype "passive"))
      (node (ref "LS40") (pin "1") (pinfunction "1_1") (pintype "passive"))
    )
    (net (code "41") (name "Net-(J6-Pad2)") (class "Default")
      (node (ref "J6") (pin "2") (pinfunction "2_2") (pintype "passive"))
      (node (ref "LS41") (pin "1") (pinfunction "1_1") (pintype "passive"))
    )
    (net (code "42") (name "Net-(J6-Pad4)") (class "Default")
      (node (ref "J6") (pin "4") (pinfunction "4_4") (pintype "passive"))
      (node (ref "LS42") (pin "1") (pinfunction "1_1") (pintype "passive"))
    )
    (net (code "43") (name "Net-(J6-Pad6)") (class "Default")
      (node (ref "J6") (pin "6") (pinfunction "6_6") (pintype "passive"))
      (node (ref "LS43") (pin "1") (pinfunction "1_1") (pintype "passive"))
    )
    (net (code "44") (name "Net-(J6-Pad8)") (class "Default")
      (node (ref "J6") (pin "8") (pinfunction "8_8") (pintype "passive"))
      (node (ref "LS44") (pin "1") (pinfunction "1_1") (pintype "passive"))
    )
    (net (code "45") (name "Net-(J6-Pad10)") (class "Default")
      (node (ref "J6") (pin "10") (pinfunction "10_10") (pintype "passive"))
      (node (ref "LS45") (pin "1") (pinfunction "1_1") (pintype "passive"))
    )
    (net (code "46") (name "Net-(J6-Pad12)") (class "Default")
      (node (ref "J6") (pin "12") (pinfunction "12_12") (pintype "passive"))
      (node (ref "LS46") (pin "1") (pinfunction "1_1") (pintype "passive"))
    )
    (net (code "47") (name "Net-(J6-Pad14)") (class "Default")
      (node (ref "J6") (pin "14") (pinfunction "14_14") (pintype "passive"))
      (node (ref "LS47") (pin "1") (pinfunction "1_1") (pintype "passive"))
    )
    (net (code "48") (name "Net-(J6-Pad16)") (class "Default")
      (node (ref "J6") (pin "16") (pinfunction "16_16") (pintype "passive"))
      (node (ref "LS48") (pin "1") (pinfunction "1_1") (pintype "passive"))
    )
    (net (code "49") (name "Net-(J7-Pad2)") (class "Default")
      (node (ref "J7") (pin "2") (pinfunction "2_2") (pintype "passive"))
      (node (ref "LS49") (pin "1") (pinfunction "1_1") (pintype "passive"))
    )
    (net (code "50") (name "Net-(J7-Pad6)") (class "Default")
      (node (ref "J7") (pin "6") (pinfunction "6_6") (pintype "passive"))
      (node (ref "LS51") (pin "1") (pinfunction "1_1") (pintype "passive"))
    )
    (net (code "51") (name "Net-(J7-Pad8)") (class "Default")
      (node (ref "J7") (pin "8") (pinfunction "8_8") (pintype "passive"))
      (node (ref "LS52") (pin "1") (pinfunction "1_1") (pintype "passive"))
    )
    (net (code "52") (name "Net-(J7-Pad10)") (class "Default")
      (node (ref "J7") (pin "10") (pinfunction "10_10") (pintype "passive"))
      (node (ref "LS53") (pin "1") (pinfunction "1_1") (pintype "passive"))
    )
    (net (code "53") (name "Net-(J7-Pad12)") (class "Default")
      (node (ref "J7") (pin "12") (pinfunction "12_12") (pintype "passive"))
      (node (ref "LS54") (pin "1") (pinfunction "1_1") (pintype "passive"))
    )
    (net (code "54") (name "Net-(J7-Pad14)") (class "Default")
      (node (ref "J7") (pin "14") (pinfunction "14_14") (pintype "passive"))
      (node (ref "LS55") (pin "1") (pinfunction "1_1") (pintype "passive"))
    )
    (net (code "55") (name "Net-(J7-Pad16)") (class "Default")
      (node (ref "J7") (pin "16") (pinfunction "16_16") (pintype "passive"))
      (node (ref "LS56") (pin "1") (pinfunction "1_1") (pintype "passive"))
    )
    (net (code "56") (name "Net-(J8-Pad2)") (class "Default")
      (node (ref "J8") (pin "2") (pinfunction "2_2") (pintype "passive"))
      (node (ref "LS57") (pin "1") (pinfunction "1_1") (pintype "passive"))
    )
    (net (code "57") (name "Net-(J8-Pad4)") (class "Default")
      (node (ref "J8") (pin "4") (pinfunction "4_4") (pintype "passive"))
      (node (ref "LS58") (pin "1") (pinfunction "1_1") (pintype "passive"))
    )
    (net (code "58") (name "Net-(J8-Pad6)") (class "Default")
      (node (ref "J8") (pin "6") (pinfunction "6_6") (pintype "passive"))
      (node (ref "LS59") (pin "1") (pinfunction "1_1") (pintype "passive"))
    )
    (net (code "59") (name "Net-(J8-Pad8)") (class "Default")
      (node (ref "J8") (pin "8") (pinfunction "8_8") (pintype "passive"))
      (node (ref "LS60") (pin "1") (pinfunction "1_1") (pintype "passive"))
    )
    (net (code "60") (name "Net-(J8-Pad10)") (class "Default")
      (node (ref "J8") (pin "10") (pinfunction "10_10") (pintype "passive"))
      (node (ref "LS61") (pin "1") (pinfunction "1_1") (pintype "passive"))
    )
    (net (code "61") (name "Net-(J8-Pad12)") (class "Default")
      (node (ref "J8") (pin "12") (pinfunction "12_12") (pintype "passive"))
      (node (ref "LS62") (pin "1") (pinfunction "1_1") (pintype "passive"))
    )
    (net (code "62") (name "Net-(J8-Pad14)") (class "Default")
      (node (ref "J8") (pin "14") (pinfunction "14_14") (pintype "passive"))
      (node (ref "LS63") (pin "1") (pinfunction "1_1") (pintype "passive"))
    )
    (net (code "63") (name "Net-(J8-Pad16)") (class "Default")
      (node (ref "J8") (pin "16") (pinfunction "16_16") (pintype "passive"))
      (node (ref "LS64") (pin "1") (pinfunction "1_1") (pintype "passive"))
    )
    (net (code "64") (name "unconnected-(J4-Pad4)") (class "Default")
      (node (ref "J4") (pin "4") (pinfunction "4_4") (pintype "passive"))
    )
    (net (code "65") (name "unconnected-(J7-Pad4)") (class "Default")
      (node (ref "J7") (pin "4") (pinfunction "4_4") (pintype "passive"))
    )
  )
)
